# SCH_Power_Jack_V2_00.net
KiCad netlist of a schematic drawn in Altium Designer
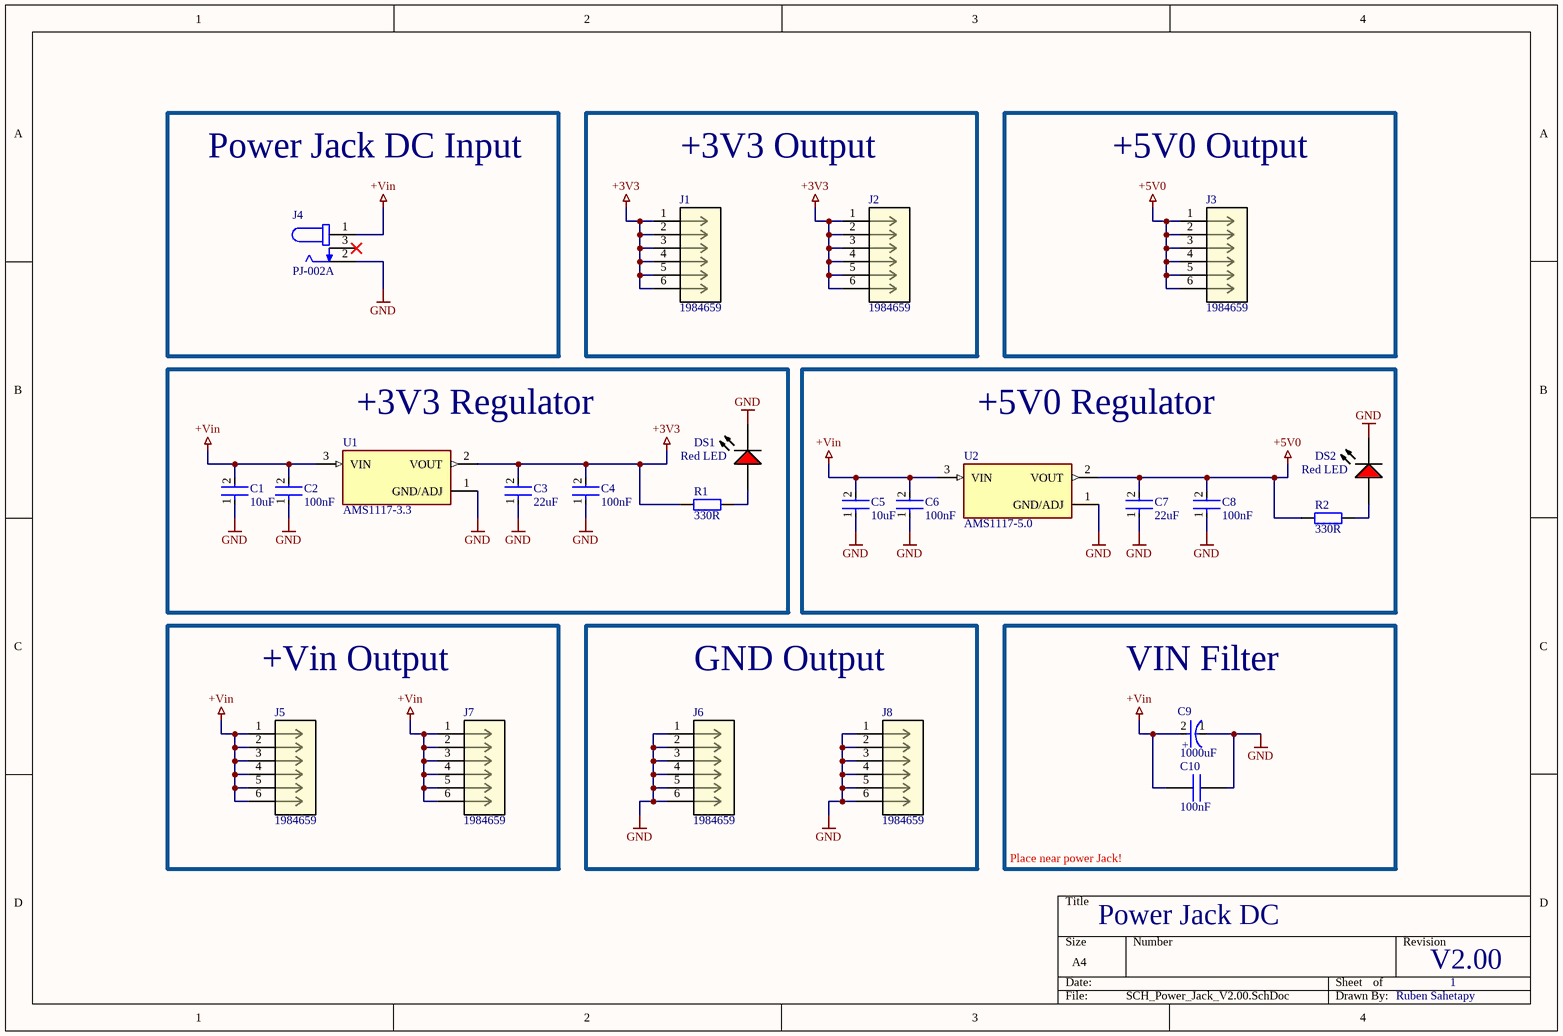
[diagram p0: SCH_Power_Jack_V2.00.SchDoc]

(export (version "E")
  (design (tool "Eeschema 10.0.6"))
  (components
    (comp (ref "C1")
      (value "10uF")
      (footprint "FP-C0805C-DG-MFG")
      (description "CAP CER 10UF 10V X5R 0805")
      (fields (field (name "TOLERANCE") "10%") (field (name "MANUFACTURER PART NUMBER") "C0805C106K8PACTU"))
      (libsource (lib "Altium Content Vault") (part "11868f565c42a9108669ba33697ecf6"))
    )
    (comp (ref "C2")
      (value "100nF")
      (footprint "FP-C0805C-DG-MFG")
      (description "CAP CER 10UF 10V X5R 0805")
      (fields (field (name "TOLERANCE") "10%") (field (name "MANUFACTURER PART NUMBER") "C0805C106K8PACTU"))
      (libsource (lib "Altium Content Vault") (part "11868f565c42a9108669ba33697ecf6"))
    )
    (comp (ref "C3")
      (value "22uF")
      (footprint "FP-C0805C-DG-MFG")
      (description "CAP CER 10UF 10V X5R 0805")
      (fields (field (name "TOLERANCE") "10%") (field (name "MANUFACTURER PART NUMBER") "C0805C106K8PACTU"))
      (libsource (lib "Altium Content Vault") (part "11868f565c42a9108669ba33697ecf6"))
    )
    (comp (ref "C4")
      (value "100nF")
      (footprint "FP-C0805C-DG-MFG")
      (description "CAP CER 10UF 10V X5R 0805")
      (fields (field (name "TOLERANCE") "10%") (field (name "MANUFACTURER PART NUMBER") "C0805C106K8PACTU"))
      (libsource (lib "Altium Content Vault") (part "11868f565c42a9108669ba33697ecf6"))
    )
    (comp (ref "C5")
      (value "10uF")
      (footprint "FP-C0805C-DG-MFG")
      (description "CAP CER 10UF 10V X5R 0805")
      (fields (field (name "TOLERANCE") "10%") (field (name "MANUFACTURER PART NUMBER") "C0805C106K8PACTU"))
      (libsource (lib "Altium Content Vault") (part "11868f565c42a9108669ba33697ecf6"))
    )
    (comp (ref "C6")
      (value "100nF")
      (footprint "FP-C0805C-DG-MFG")
      (description "CAP CER 10UF 10V X5R 0805")
      (fields (field (name "TOLERANCE") "10%") (field (name "MANUFACTURER PART NUMBER") "C0805C106K8PACTU"))
      (libsource (lib "Altium Content Vault") (part "11868f565c42a9108669ba33697ecf6"))
    )
    (comp (ref "C7")
      (value "22uF")
      (footprint "FP-C0805C-DG-MFG")
      (description "CAP CER 10UF 10V X5R 0805")
      (fields (field (name "TOLERANCE") "10%") (field (name "MANUFACTURER PART NUMBER") "C0805C106K8PACTU"))
      (libsource (lib "Altium Content Vault") (part "11868f565c42a9108669ba33697ecf6"))
    )
    (comp (ref "C8")
      (value "100nF")
      (footprint "FP-C0805C-DG-MFG")
      (description "CAP CER 10UF 10V X5R 0805")
      (fields (field (name "TOLERANCE") "10%") (field (name "MANUFACTURER PART NUMBER") "C0805C106K8PACTU"))
      (libsource (lib "Altium Content Vault") (part "11868f565c42a9108669ba33697ecf6"))
    )
    (comp (ref "C9")
      (value "1000uF")
      (footprint "FP-OS-CON-SMT-F10-MFG")
      (description "CAP ALUM POLY 1000UF 20% 16V SMD")
      (libsource (lib "Altium Content Vault") (part "203bc49f2ac43e59fd269a8c329ed05"))
    )
    (comp (ref "C10")
      (value "100nF")
      (footprint "CAP0805")
      (description "Capacitor 0805")
      (fields (field (name "MF") "Yageo") (field (name "MP") "CC0805KRX7R9BB104"))
      (libsource (lib "MarbleLib") (part "C"))
    )
    (comp (ref "DS1")
      (value "Red LED")
      (footprint "LUMX-SML-LX1206IC_V")
      (description "LED Red, 65 mW, -40 to 85 degC, 2-Pin SMD, RoHS, Tape and Reel")
      (fields (field (name "MANUFACTURER") "Lumex") (field (name "PART NO") "SML-LX1206IC-TR"))
      (libsource (lib "Altium Content Vault") (part "LED-RED-AK-2"))
    )
    (comp (ref "DS2")
      (value "Red LED")
      (footprint "LUMX-SML-LX1206IC_V")
      (description "LED Red, 65 mW, -40 to 85 degC, 2-Pin SMD, RoHS, Tape and Reel")
      (fields (field (name "MANUFACTURER") "Lumex") (field (name "PART NO") "SML-LX1206IC-TR"))
      (libsource (lib "Altium Content Vault") (part "LED-RED-AK-2"))
    )
    (comp (ref "J1")
      (value "1984659")
      (footprint "CONN_1984659_PXC")
      (description "6 Position Wire to Board Terminal Block Horizontal with Board 0.138\" (3.50mm) Through Hole")
      (fields (field (name "COPYRIGHT") "Copyright (C) 2025 Ultra Librarian. All rights reserved."))
      (libsource (lib "MarbleLib") (part "1984659"))
    )
    (comp (ref "J2")
      (value "1984659")
      (footprint "CONN_1984659_PXC")
      (description "6 Position Wire to Board Terminal Block Horizontal with Board 0.138\" (3.50mm) Through Hole")
      (fields (field (name "COPYRIGHT") "Copyright (C) 2025 Ultra Librarian. All rights reserved."))
      (libsource (lib "MarbleLib") (part "1984659"))
    )
    (comp (ref "J3")
      (value "1984659")
      (footprint "CONN_1984659_PXC")
      (description "6 Position Wire to Board Terminal Block Horizontal with Board 0.138\" (3.50mm) Through Hole")
      (fields (field (name "COPYRIGHT") "Copyright (C) 2025 Ultra Librarian. All rights reserved."))
      (libsource (lib "MarbleLib") (part "1984659"))
    )
    (comp (ref "J4")
      (value "PJ-002A")
      (footprint "CUI_PJ-002A")
      (description "DC Power Connectors Power Jacks 2x5.5mm")
      (fields (field (name "MF") "Same Sky"))
      (libsource (lib "MarbleLib") (part "PJ-002A"))
    )
    (comp (ref "J5")
      (value "1984659")
      (footprint "CONN_1984659_PXC")
      (description "6 Position Wire to Board Terminal Block Horizontal with Board 0.138\" (3.50mm) Through Hole")
      (fields (field (name "COPYRIGHT") "Copyright (C) 2025 Ultra Librarian. All rights reserved."))
      (libsource (lib "MarbleLib") (part "1984659"))
    )
    (comp (ref "J6")
      (value "1984659")
      (footprint "CONN_1984659_PXC")
      (description "6 Position Wire to Board Terminal Block Horizontal with Board 0.138\" (3.50mm) Through Hole")
      (fields (field (name "COPYRIGHT") "Copyright (C) 2025 Ultra Librarian. All rights reserved."))
      (libsource (lib "MarbleLib") (part "1984659"))
    )
    (comp (ref "J7")
      (value "1984659")
      (footprint "CONN_1984659_PXC")
      (description "6 Position Wire to Board Terminal Block Horizontal with Board 0.138\" (3.50mm) Through Hole")
      (fields (field (name "COPYRIGHT") "Copyright (C) 2025 Ultra Librarian. All rights reserved."))
      (libsource (lib "MarbleLib") (part "1984659"))
    )
    (comp (ref "J8")
      (value "1984659")
      (footprint "CONN_1984659_PXC")
      (description "6 Position Wire to Board Terminal Block Horizontal with Board 0.138\" (3.50mm) Through Hole")
      (fields (field (name "COPYRIGHT") "Copyright (C) 2025 Ultra Librarian. All rights reserved."))
      (libsource (lib "MarbleLib") (part "1984659"))
    )
    (comp (ref "R1")
      (value "330R")
      (footprint "RES1206")
      (description "Resistor 1206")
      (libsource (lib "MarbleLib") (part "R"))
    )
    (comp (ref "R2")
      (value "330R")
      (footprint "RES1206")
      (description "Resistor 1206")
      (libsource (lib "MarbleLib") (part "R"))
    )
    (comp (ref "U1")
      (value "AMS1117-3.3")
      (footprint "SOT229P700X180-4N")
      (description "Linearer Spannungsregler, 800 mA, 15 V")
      (fields (field (name "MF") "Advanced Monolithic Systems"))
      (libsource (lib "MarbleLib") (part "AMS1117-3.3"))
    )
    (comp (ref "U2")
      (value "AMS1117-5.0")
      (footprint "SOT229P700X180-4N")
      (description "Linearer Spannungsregler, 800 mA, 15 V")
      (fields (field (name "MF") "Advanced Monolithic Systems") (field (name "MP") "AMS1117-3.3"))
      (libsource (lib "MarbleLib") (part "AMS1117-3.3"))
    )
  )
  (nets
    (net (code "1") (name "+3V3") (class "Default")
      (node (ref "C3") (pin "2") (pinfunction "2_2") (pintype "passive"))
      (node (ref "C4") (pin "2") (pinfunction "2_2") (pintype "passive"))
      (node (ref "J1") (pin "1") (pinfunction "1_1") (pintype "passive"))
      (node (ref "J1") (pin "2") (pinfunction "2_2") (pintype "passive"))
      (node (ref "J1") (pin "3") (pinfunction "3_3") (pintype "passive"))
      (node (ref "J1") (pin "4") (pinfunction "4_4") (pintype "passive"))
      (node (ref "J1") (pin "5") (pinfunction "5_5") (pintype "passive"))
      (node (ref "J1") (pin "6") (pinfunction "6_6") (pintype "passive"))
      (node (ref "J2") (pin "1") (pinfunction "1_1") (pintype "passive"))
      (node (ref "J2") (pin "2") (pinfunction "2_2") (pintype "passive"))
      (node (ref "J2") (pin "3") (pinfunction "3_3") (pintype "passive"))
      (node (ref "J2") (pin "4") (pinfunction "4_4") (pintype "passive"))
      (node (ref "J2") (pin "5") (pinfunction "5_5") (pintype "passive"))
      (node (ref "J2") (pin "6") (pinfunction "6_6") (pintype "passive"))
      (node (ref "R1") (pin "1") (pinfunction "1_1") (pintype "passive"))
      (node (ref "U1") (pin "2") (pinfunction "VOUT_2") (pintype "output"))
    )
    (net (code "2") (name "+5V0") (class "Default")
      (node (ref "C7") (pin "2") (pinfunction "2_2") (pintype "passive"))
      (node (ref "C8") (pin "2") (pinfunction "2_2") (pintype "passive"))
      (node (ref "J3") (pin "1") (pinfunction "1_1") (pintype "passive"))
      (node (ref "J3") (pin "2") (pinfunction "2_2") (pintype "passive"))
      (node (ref "J3") (pin "3") (pinfunction "3_3") (pintype "passive"))
      (node (ref "J3") (pin "4") (pinfunction "4_4") (pintype "passive"))
      (node (ref "J3") (pin "5") (pinfunction "5_5") (pintype "passive"))
      (node (ref "J3") (pin "6") (pinfunction "6_6") (pintype "passive"))
      (node (ref "R2") (pin "1") (pinfunction "1_1") (pintype "passive"))
      (node (ref "U2") (pin "2") (pinfunction "VOUT_2") (pintype "output"))
    )
    (net (code "3") (name "+Vin") (class "Default")
      (node (ref "C1") (pin "2") (pinfunction "2_2") (pintype "passive"))
      (node (ref "C10") (pin "1") (pinfunction "1_1") (pintype "passive"))
      (node (ref "C2") (pin "2") (pinfunction "2_2") (pintype "passive"))
      (node (ref "C5") (pin "2") (pinfunction "2_2") (pintype "passive"))
      (node (ref "C6") (pin "2") (pinfunction "2_2") (pintype "passive"))
      (node (ref "C9") (pin "2") (pinfunction "A_2") (pintype "passive"))
      (node (ref "J4") (pin "1") (pinfunction "1_1") (pintype "passive"))
      (node (ref "J5") (pin "1") (pinfunction "1_1") (pintype "passive"))
      (node (ref "J5") (pin "2") (pinfunction "2_2") (pintype "passive"))
      (node (ref "J5") (pin "3") (pinfunction "3_3") (pintype "passive"))
      (node (ref "J5") (pin "4") (pinfunction "4_4") (pintype "passive"))
      (node (ref "J5") (pin "5") (pinfunction "5_5") (pintype "passive"))
      (node (ref "J5") (pin "6") (pinfunction "6_6") (pintype "passive"))
      (node (ref "J7") (pin "1") (pinfunction "1_1") (pintype "passive"))
      (node (ref "J7") (pin "2") (pinfunction "2_2") (pintype "passive"))
      (node (ref "J7") (pin "3") (pinfunction "3_3") (pintype "passive"))
      (node (ref "J7") (pin "4") (pinfunction "4_4") (pintype "passive"))
      (node (ref "J7") (pin "5") (pinfunction "5_5") (pintype "passive"))
      (node (ref "J7") (pin "6") (pinfunction "6_6") (pintype "passive"))
      (node (ref "U1") (pin "3") (pinfunction "VIN_3") (pintype "input"))
      (node (ref "U2") (pin "3") (pinfunction "VIN_3") (pintype "input"))
    )
    (net (code "4") (name "GND") (class "Default")
      (node (ref "C1") (pin "1") (pinfunction "1_1") (pintype "passive"))
      (node (ref "C10") (pin "2") (pinfunction "2_2") (pintype "passive"))
      (node (ref "C2") (pin "1") (pinfunction "1_1") (pintype "passive"))
      (node (ref "C3") (pin "1") (pinfunction "1_1") (pintype "passive"))
      (node (ref "C4") (pin "1") (pinfunction "1_1") (pintype "passive"))
      (node (ref "C5") (pin "1") (pinfunction "1_1") (pintype "passive"))
      (node (ref "C6") (pin "1") (pinfunction "1_1") (pintype "passive"))
      (node (ref "C7") (pin "1") (pinfunction "1_1") (pintype "passive"))
      (node (ref "C8") (pin "1") (pinfunction "1_1") (pintype "passive"))
      (node (ref "C9") (pin "1") (pinfunction "C_1") (pintype "passive"))
      (node (ref "DS1") (pin "2") (pinfunction "K_2") (pintype "passive"))
      (node (ref "DS2") (pin "2") (pinfunction "K_2") (pintype "passive"))
      (node (ref "J4") (pin "2") (pinfunction "2_2") (pintype "passive"))
      (node (ref "J6") (pin "1") (pinfunction "1_1") (pintype "passive"))
      (node (ref "J6") (pin "2") (pinfunction "2_2") (pintype "passive"))
      (node (ref "J6") (pin "3") (pinfunction "3_3") (pintype "passive"))
      (node (ref "J6") (pin "4") (pinfunction "4_4") (pintype "passive"))
      (node (ref "J6") (pin "5") (pinfunction "5_5") (pintype "passive"))
      (node (ref "J6") (pin "6") (pinfunction "6_6") (pintype "passive"))
      (node (ref "J8") (pin "1") (pinfunction "1_1") (pintype "passive"))
      (node (ref "J8") (pin "2") (pinfunction "2_2") (pintype "passive"))
      (node (ref "J8") (pin "3") (pinfunction "3_3") (pintype "passive"))
      (node (ref "J8") (pin "4") (pinfunction "4_4") (pintype "passive"))
      (node (ref "J8") (pin "5") (pinfunction "5_5") (pintype "passive"))
      (node (ref "J8") (pin "6") (pinfunction "6_6") (pintype "passive"))
      (node (ref "U1") (pin "1") (pinfunction "GND/ADJ_1") (pintype "power_in"))
      (node (ref "U2") (pin "1") (pinfunction "GND/ADJ_1") (pintype "power_in"))
    )
    (net (code "5") (name "Net-(DS1-A)") (class "Default")
      (node (ref "DS1") (pin "1") (pinfunction "A_1") (pintype "passive"))
      (node (ref "R1") (pin "2") (pinfunction "2_2") (pintype "passive"))
    )
    (net (code "6") (name "Net-(DS2-A)") (class "Default")
      (node (ref "DS2") (pin "1") (pinfunction "A_1") (pintype "passive"))
      (node (ref "R2") (pin "2") (pinfunction "2_2") (pintype "passive"))
    )
    (net (code "7") (name "unconnected-(J4-Pad3)") (class "Default")
      (node (ref "J4") (pin "3") (pinfunction "3_3") (pintype "passive+no_connect"))
    )
  )
)
